# 06-AD9546_TimestampInputs.net
KiCad netlist of a schematic drawn in Altium Designer
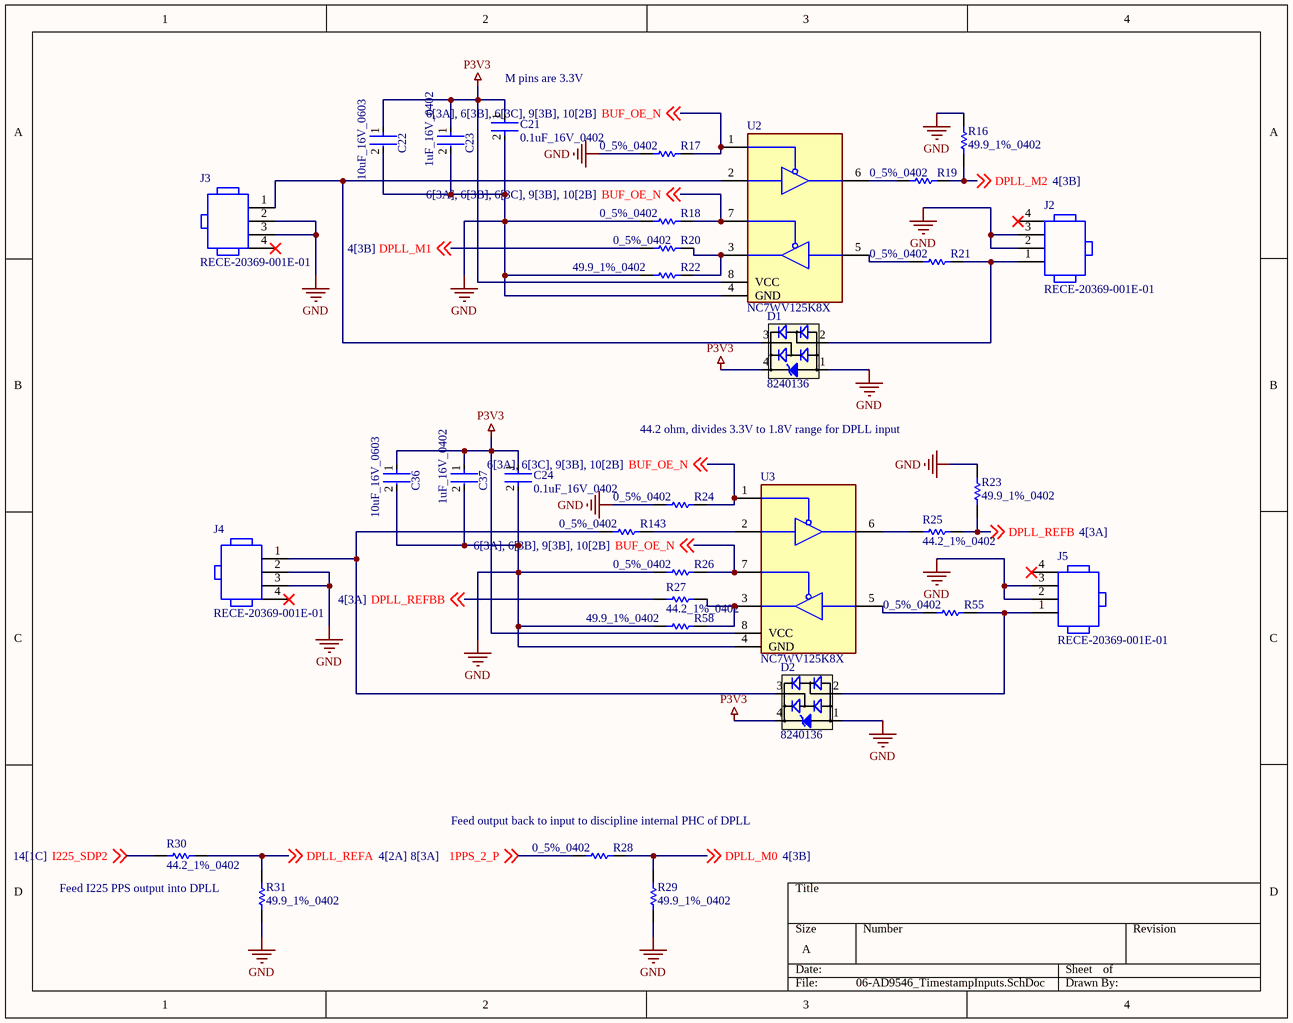
[diagram p0: 06-AD9546_TimestampInputs.SchDoc]

(export (version "E")
  (design (tool "Eeschema 10.0.6"))
  (components
    (comp (ref "C21")
      (value "GRM155R71C104KA88D")
      (footprint "FP-GRM15-MFG")
      (description "CAP CER 0.1UF 16V X7R 0402")
      (fields
        (field (name "TOLERANCE") "10%")
        (field (name "OCTOPART") "https://octopart.com/grm155r71c104ka88d-murata-196880")
        (field (name "DIGIKEY DESCRIPTION") "0.1uF_16V_0402")
      )
      (libsource (lib "Altium Content Vault") (part "236180d848d6139a670b325ea6854c9"))
    )
    (comp (ref "C22")
      (value "10uF_16V_0603")
      (footprint "FP-C1608-MFG")
      (description "CAP CER 10UF 16V X5R 0603")
      (fields
        (field (name "OCTOPART") "https://octopart.com/c1608x5r1c106m080ab-tdk-26013480")
        (field (name "MANUFACTURER") "TDK Corporation")
      )
      (libsource (lib "Altium Content Vault") (part "11868f565c42a9108669ba33697ecf6"))
    )
    (comp (ref "C23")
      (value "1uF_16V_0402")
      (footprint "FP-0402-L_1_0_0_05-W_0_5-IPC_C")
      (description "None")
      (fields (field (name "TOLERANCE") "20%") (field (name "VOLTAGE") "16V"))
      (libsource (lib "Altium Content Vault") (part "b4654b650e69147ec39a6b967a45e02"))
    )
    (comp (ref "C24")
      (value "GRM155R71C104KA88D")
      (footprint "FP-GRM15-MFG")
      (description "CAP CER 0.1UF 16V X7R 0402")
      (fields
        (field (name "TOLERANCE") "10%")
        (field (name "OCTOPART") "https://octopart.com/grm155r71c104ka88d-murata-196880")
        (field (name "DIGIKEY DESCRIPTION") "0.1uF_16V_0402")
      )
      (libsource (lib "Altium Content Vault") (part "236180d848d6139a670b325ea6854c9"))
    )
    (comp (ref "C36")
      (value "10uF_16V_0603")
      (footprint "FP-C1608-MFG")
      (description "CAP CER 10UF 16V X5R 0603")
      (fields
        (field (name "OCTOPART") "https://octopart.com/c1608x5r1c106m080ab-tdk-26013480")
        (field (name "MANUFACTURER") "TDK Corporation")
      )
      (libsource (lib "Altium Content Vault") (part "11868f565c42a9108669ba33697ecf6"))
    )
    (comp (ref "C37")
      (value "1uF_16V_0402")
      (footprint "FP-0402-L_1_0_0_05-W_0_5-IPC_C")
      (description "None")
      (fields (field (name "TOLERANCE") "20%") (field (name "VOLTAGE") "16V"))
      (libsource (lib "Altium Content Vault") (part "b4654b650e69147ec39a6b967a45e02"))
    )
    (comp (ref "D1")
      (value "8240136")
      (footprint "SOT143-4L")
      (description "TVS Diode WE-TVS-HS, VRWM=3.3V")
      (fields (field (name "MANUFACTURER") "Wuerth Elektronik"))
      (libsource (lib "Altium Content Vault") (part "WE-TVS-HS-4"))
    )
    (comp (ref "D2")
      (value "8240136")
      (footprint "SOT143-4L")
      (description "TVS Diode WE-TVS-HS, VRWM=3.3V")
      (fields (field (name "MANUFACTURER") "Wuerth Elektronik"))
      (libsource (lib "Altium Content Vault") (part "WE-TVS-HS-4"))
    )
    (comp (ref "J2")
      (value "RECE-20369-001E-01")
      (footprint "TG-RECE-20369-001E-4_V")
      (description "RF Connector, Onboard Receptacle, IPEX MHFIII")
      (fields (field (name "MANUFACTURER") "Taoglas"))
      (libsource (lib "Altium Content Vault") (part "TG-RECE-20369-001E-01-4"))
    )
    (comp (ref "J3")
      (value "RECE-20369-001E-01")
      (footprint "TG-RECE-20369-001E-4_V")
      (description "RF Connector, Onboard Receptacle, IPEX MHFIII")
      (fields (field (name "MANUFACTURER") "Taoglas"))
      (libsource (lib "Altium Content Vault") (part "TG-RECE-20369-001E-01-4"))
    )
    (comp (ref "J4")
      (value "RECE-20369-001E-01")
      (footprint "TG-RECE-20369-001E-4_V")
      (description "RF Connector, Onboard Receptacle, IPEX MHFIII")
      (fields (field (name "MANUFACTURER") "Taoglas"))
      (libsource (lib "Altium Content Vault") (part "TG-RECE-20369-001E-01-4"))
    )
    (comp (ref "J5")
      (value "RECE-20369-001E-01")
      (footprint "TG-RECE-20369-001E-4_V")
      (description "RF Connector, Onboard Receptacle, IPEX MHFIII")
      (fields (field (name "MANUFACTURER") "Taoglas"))
      (libsource (lib "Altium Content Vault") (part "TG-RECE-20369-001E-01-4"))
    )
    (comp (ref "R16")
      (value "49.9_1%_0402")
      (footprint "RESC1005X40X25NL05T05")
      (fields (field (name "MANUFACTURER") "Panasonic") (field (name "PART NUMBER") "ERJ-2RKF49R9X"))
      (libsource (lib "Altium Content Vault") (part "RES"))
    )
    (comp (ref "R17")
      (value "0_5%_0402")
      (footprint "RESC1005X40X25LL10T10")
      (fields (field (name "MANUFACTURER") "KOA Speer") (field (name "PART NUMBER") "RK73Z1ETTP"))
      (libsource (lib "Altium Content Vault") (part "RES"))
    )
    (comp (ref "R18")
      (value "0_5%_0402")
      (footprint "RESC1005X40X25LL10T10")
      (fields (field (name "MANUFACTURER") "KOA Speer") (field (name "PART NUMBER") "RK73Z1ETTP"))
      (libsource (lib "Altium Content Vault") (part "RES"))
    )
    (comp (ref "R19")
      (value "0_5%_0402")
      (footprint "RESC1005X40X25LL10T10")
      (fields (field (name "MANUFACTURER") "KOA Speer") (field (name "PART NUMBER") "RK73Z1ETTP"))
      (libsource (lib "Altium Content Vault") (part "RES"))
    )
    (comp (ref "R20")
      (value "0_5%_0402")
      (footprint "RESC1005X40X25LL10T10")
      (fields (field (name "MANUFACTURER") "KOA Speer") (field (name "PART NUMBER") "RK73Z1ETTP"))
      (libsource (lib "Altium Content Vault") (part "RES"))
    )
    (comp (ref "R21")
      (value "0_5%_0402")
      (footprint "RESC1005X40X25LL10T10")
      (fields (field (name "MANUFACTURER") "KOA Speer") (field (name "PART NUMBER") "RK73Z1ETTP"))
      (libsource (lib "Altium Content Vault") (part "RES"))
    )
    (comp (ref "R22")
      (value "49.9_1%_0402")
      (footprint "RESC1005X40X25NL05T05")
      (fields (field (name "MANUFACTURER") "Panasonic") (field (name "PART NUMBER") "ERJ-2RKF49R9X"))
      (libsource (lib "Altium Content Vault") (part "RES"))
    )
    (comp (ref "R23")
      (value "49.9_1%_0402")
      (footprint "RESC1005X40X25NL05T05")
      (fields (field (name "MANUFACTURER") "Panasonic") (field (name "PART NUMBER") "ERJ-2RKF49R9X"))
      (libsource (lib "Altium Content Vault") (part "RES"))
    )
    (comp (ref "R24")
      (value "0_5%_0402")
      (footprint "RESC1005X40X25LL10T10")
      (fields (field (name "MANUFACTURER") "KOA Speer") (field (name "PART NUMBER") "RK73Z1ETTP"))
      (libsource (lib "Altium Content Vault") (part "RES"))
    )
    (comp (ref "R25")
      (value "44.2_1%_0402")
      (footprint "RESC1005X40X25LL05T05")
      (fields (field (name "MANUFACTURER") "Vishay Dale") (field (name "PART NUMBER") "CRCW040244R2FKED"))
      (libsource (lib "Altium Content Vault") (part "RES"))
    )
    (comp (ref "R26")
      (value "0_5%_0402")
      (footprint "RESC1005X40X25LL10T10")
      (fields (field (name "MANUFACTURER") "KOA Speer") (field (name "PART NUMBER") "RK73Z1ETTP"))
      (libsource (lib "Altium Content Vault") (part "RES"))
    )
    (comp (ref "R27")
      (value "44.2_1%_0402")
      (footprint "RESC1005X40X25LL05T05")
      (fields (field (name "MANUFACTURER") "Vishay Dale") (field (name "PART NUMBER") "CRCW040244R2FKED"))
      (libsource (lib "Altium Content Vault") (part "RES"))
    )
    (comp (ref "R28")
      (value "0_5%_0402")
      (footprint "RESC1005X40X25LL10T10")
      (fields (field (name "MANUFACTURER") "KOA Speer") (field (name "PART NUMBER") "RK73Z1ETTP"))
      (libsource (lib "Altium Content Vault") (part "RES"))
    )
    (comp (ref "R29")
      (value "49.9_1%_0402")
      (footprint "RESC1005X40X25NL05T05")
      (fields (field (name "MANUFACTURER") "Panasonic") (field (name "PART NUMBER") "ERJ-2RKF49R9X"))
      (libsource (lib "Altium Content Vault") (part "RES"))
    )
    (comp (ref "R30")
      (value "44.2_1%_0402")
      (footprint "RESC1005X40X25LL05T05")
      (fields (field (name "MANUFACTURER") "Vishay Dale") (field (name "PART NUMBER") "CRCW040244R2FKED"))
      (libsource (lib "Altium Content Vault") (part "RES"))
    )
    (comp (ref "R31")
      (value "49.9_1%_0402")
      (footprint "RESC1005X40X25NL05T05")
      (fields (field (name "MANUFACTURER") "Panasonic") (field (name "PART NUMBER") "ERJ-2RKF49R9X"))
      (libsource (lib "Altium Content Vault") (part "RES"))
    )
    (comp (ref "R55")
      (value "0_5%_0402")
      (footprint "RESC1005X40X25LL10T10")
      (fields (field (name "MANUFACTURER") "KOA Speer") (field (name "PART NUMBER") "RK73Z1ETTP"))
      (libsource (lib "Altium Content Vault") (part "RES"))
    )
    (comp (ref "R58")
      (value "49.9_1%_0402")
      (footprint "RESC1005X40X25NL05T05")
      (fields (field (name "MANUFACTURER") "Panasonic") (field (name "PART NUMBER") "ERJ-2RKF49R9X"))
      (libsource (lib "Altium Content Vault") (part "RES"))
    )
    (comp (ref "R143")
      (value "0_5%_0402")
      (footprint "RESC1005X40X25LL10T10")
      (fields (field (name "MANUFACTURER") "KOA Speer") (field (name "PART NUMBER") "RK73Z1ETTP"))
      (libsource (lib "Altium Content Vault") (part "RES"))
    )
    (comp (ref "U2")
      (value "NC7WV125K8X")
      (footprint "NC7WV125")
      (description "Integrated Circuit")
      (fields (field (name "MOUSER PART NUMBER") "512-NC7WV125K8X"))
      (libsource (lib "SamacSys") (part "NC7WV125K8X"))
    )
    (comp (ref "U3")
      (value "NC7WV125K8X")
      (footprint "NC7WV125")
      (description "Integrated Circuit")
      (fields (field (name "MOUSER PART NUMBER") "512-NC7WV125K8X"))
      (libsource (lib "SamacSys") (part "NC7WV125K8X"))
    )
  )
  (nets
    (net (code "1") (name "1PPS_2_P") (class "Default")
      (node (ref "R28") (pin "1") (pinfunction "1_1") (pintype "passive"))
    )
    (net (code "2") (name "BUF_OE_N") (class "Default")
      (node (ref "R17") (pin "2") (pinfunction "2_2") (pintype "passive"))
      (node (ref "R18") (pin "2") (pinfunction "2_2") (pintype "passive"))
      (node (ref "R24") (pin "2") (pinfunction "2_2") (pintype "passive"))
      (node (ref "R26") (pin "2") (pinfunction "2_2") (pintype "passive"))
      (node (ref "U2") (pin "1") (pintype "passive"))
      (node (ref "U2") (pin "7") (pintype "passive"))
      (node (ref "U3") (pin "1") (pintype "passive"))
      (node (ref "U3") (pin "7") (pintype "passive"))
    )
    (net (code "3") (name "DPLL_M0") (class "Default")
      (node (ref "R28") (pin "2") (pinfunction "2_2") (pintype "passive"))
      (node (ref "R29") (pin "2") (pinfunction "2_2") (pintype "passive"))
    )
    (net (code "4") (name "DPLL_M1") (class "Default")
      (node (ref "R20") (pin "1") (pinfunction "1_1") (pintype "passive"))
    )
    (net (code "5") (name "DPLL_M2") (class "Default")
      (node (ref "R16") (pin "1") (pinfunction "1_1") (pintype "passive"))
      (node (ref "R19") (pin "2") (pinfunction "2_2") (pintype "passive"))
    )
    (net (code "6") (name "DPLL_REFA") (class "Default")
      (node (ref "R30") (pin "2") (pinfunction "2_2") (pintype "passive"))
      (node (ref "R31") (pin "2") (pinfunction "2_2") (pintype "passive"))
    )
    (net (code "7") (name "DPLL_REFB") (class "Default")
      (node (ref "R23") (pin "1") (pinfunction "1_1") (pintype "passive"))
      (node (ref "R25") (pin "2") (pinfunction "2_2") (pintype "passive"))
    )
    (net (code "8") (name "DPLL_REFBB") (class "Default")
      (node (ref "R27") (pin "1") (pinfunction "1_1") (pintype "passive"))
    )
    (net (code "9") (name "GND") (class "Default")
      (node (ref "C21") (pin "2") (pinfunction "2_2") (pintype "passive"))
      (node (ref "C22") (pin "2") (pinfunction "2_2") (pintype "passive"))
      (node (ref "C23") (pin "2") (pinfunction "2_2") (pintype "passive"))
      (node (ref "C24") (pin "2") (pinfunction "2_2") (pintype "passive"))
      (node (ref "C36") (pin "2") (pinfunction "2_2") (pintype "passive"))
      (node (ref "C37") (pin "2") (pinfunction "2_2") (pintype "passive"))
      (node (ref "D1") (pin "1") (pinfunction "GND_1") (pintype "passive"))
      (node (ref "D2") (pin "1") (pinfunction "GND_1") (pintype "passive"))
      (node (ref "J2") (pin "2") (pinfunction "2_2") (pintype "passive"))
      (node (ref "J2") (pin "3") (pinfunction "3_3") (pintype "passive"))
      (node (ref "J3") (pin "2") (pinfunction "2_2") (pintype "passive"))
      (node (ref "J3") (pin "3") (pinfunction "3_3") (pintype "passive"))
      (node (ref "J4") (pin "2") (pinfunction "2_2") (pintype "passive"))
      (node (ref "J4") (pin "3") (pinfunction "3_3") (pintype "passive"))
      (node (ref "J5") (pin "2") (pinfunction "2_2") (pintype "passive"))
      (node (ref "J5") (pin "3") (pinfunction "3_3") (pintype "passive"))
      (node (ref "R16") (pin "2") (pinfunction "2_2") (pintype "passive"))
      (node (ref "R17") (pin "1") (pinfunction "1_1") (pintype "passive"))
      (node (ref "R18") (pin "1") (pinfunction "1_1") (pintype "passive"))
      (node (ref "R22") (pin "2") (pinfunction "2_2") (pintype "passive"))
      (node (ref "R23") (pin "2") (pinfunction "2_2") (pintype "passive"))
      (node (ref "R24") (pin "1") (pinfunction "1_1") (pintype "passive"))
      (node (ref "R26") (pin "1") (pinfunction "1_1") (pintype "passive"))
      (node (ref "R29") (pin "1") (pinfunction "1_1") (pintype "passive"))
      (node (ref "R31") (pin "1") (pinfunction "1_1") (pintype "passive"))
      (node (ref "R58") (pin "2") (pinfunction "2_2") (pintype "passive"))
      (node (ref "U2") (pin "4") (pinfunction "GND_4") (pintype "passive"))
      (node (ref "U3") (pin "4") (pinfunction "GND_4") (pintype "passive"))
    )
    (net (code "10") (name "I225_SDP2") (class "Default")
      (node (ref "R30") (pin "1") (pinfunction "1_1") (pintype "passive"))
    )
    (net (code "11") (name "Net-(D1-I{slash}O1)") (class "Default")
      (node (ref "D1") (pin "2") (pinfunction "I/O1_2") (pintype "passive"))
      (node (ref "J2") (pin "1") (pinfunction "1_1") (pintype "passive"))
      (node (ref "R21") (pin "2") (pinfunction "2_2") (pintype "passive"))
    )
    (net (code "12") (name "Net-(D1-I{slash}O2)") (class "Default")
      (node (ref "D1") (pin "3") (pinfunction "I/O2_3") (pintype "passive"))
      (node (ref "J3") (pin "1") (pinfunction "1_1") (pintype "passive"))
      (node (ref "U2") (pin "2") (pintype "passive"))
    )
    (net (code "13") (name "Net-(D2-I{slash}O1)") (class "Default")
      (node (ref "D2") (pin "2") (pinfunction "I/O1_2") (pintype "passive"))
      (node (ref "J5") (pin "1") (pinfunction "1_1") (pintype "passive"))
      (node (ref "R55") (pin "2") (pinfunction "2_2") (pintype "passive"))
    )
    (net (code "14") (name "Net-(D2-I{slash}O2)") (class "Default")
      (node (ref "D2") (pin "3") (pinfunction "I/O2_3") (pintype "passive"))
      (node (ref "J4") (pin "1") (pinfunction "1_1") (pintype "passive"))
      (node (ref "R143") (pin "1") (pinfunction "1_1") (pintype "passive"))
    )
    (net (code "15") (name "Net-(R19-Pad1)") (class "Default")
      (node (ref "R19") (pin "1") (pinfunction "1_1") (pintype "passive"))
      (node (ref "U2") (pin "6") (pintype "passive"))
    )
    (net (code "16") (name "Net-(R20-Pad2)") (class "Default")
      (node (ref "R20") (pin "2") (pinfunction "2_2") (pintype "passive"))
      (node (ref "R22") (pin "1") (pinfunction "1_1") (pintype "passive"))
      (node (ref "U2") (pin "3") (pintype "passive"))
    )
    (net (code "17") (name "Net-(R21-Pad1)") (class "Default")
      (node (ref "R21") (pin "1") (pinfunction "1_1") (pintype "passive"))
      (node (ref "U2") (pin "5") (pintype "passive"))
    )
    (net (code "18") (name "Net-(R25-Pad1)") (class "Default")
      (node (ref "R25") (pin "1") (pinfunction "1_1") (pintype "passive"))
      (node (ref "U3") (pin "6") (pintype "passive"))
    )
    (net (code "19") (name "Net-(R27-Pad2)") (class "Default")
      (node (ref "R27") (pin "2") (pinfunction "2_2") (pintype "passive"))
      (node (ref "R58") (pin "1") (pinfunction "1_1") (pintype "passive"))
      (node (ref "U3") (pin "3") (pintype "passive"))
    )
    (net (code "20") (name "Net-(R55-Pad1)") (class "Default")
      (node (ref "R55") (pin "1") (pinfunction "1_1") (pintype "passive"))
      (node (ref "U3") (pin "5") (pintype "passive"))
    )
    (net (code "21") (name "Net-(R143-Pad2)") (class "Default")
      (node (ref "R143") (pin "2") (pinfunction "2_2") (pintype "passive"))
      (node (ref "U3") (pin "2") (pintype "passive"))
    )
    (net (code "22") (name "P3V3") (class "Default")
      (node (ref "C21") (pin "1") (pinfunction "1_1") (pintype "passive"))
      (node (ref "C22") (pin "1") (pinfunction "1_1") (pintype "passive"))
      (node (ref "C23") (pin "1") (pinfunction "1_1") (pintype "passive"))
      (node (ref "C24") (pin "1") (pinfunction "1_1") (pintype "passive"))
      (node (ref "C36") (pin "1") (pinfunction "1_1") (pintype "passive"))
      (node (ref "C37") (pin "1") (pinfunction "1_1") (pintype "passive"))
      (node (ref "D1") (pin "4") (pinfunction "VDD_4") (pintype "passive"))
      (node (ref "D2") (pin "4") (pinfunction "VDD_4") (pintype "passive"))
      (node (ref "U2") (pin "8") (pinfunction "VCC_8") (pintype "passive"))
      (node (ref "U3") (pin "8") (pinfunction "VCC_8") (pintype "passive"))
    )
    (net (code "23") (name "unconnected-(J2-Pad4)") (class "Default")
      (node (ref "J2") (pin "4") (pinfunction "4_4") (pintype "passive+no_connect"))
    )
    (net (code "24") (name "unconnected-(J3-Pad4)") (class "Default")
      (node (ref "J3") (pin "4") (pinfunction "4_4") (pintype "passive+no_connect"))
    )
    (net (code "25") (name "unconnected-(J4-Pad4)") (class "Default")
      (node (ref "J4") (pin "4") (pinfunction "4_4") (pintype "passive+no_connect"))
    )
    (net (code "26") (name "unconnected-(J5-Pad4)") (class "Default")
      (node (ref "J5") (pin "4") (pinfunction "4_4") (pintype "passive+no_connect"))
    )
  )
)
